# 4b_-_Latching_IMD.net
KiCad netlist of a schematic drawn in Altium Designer
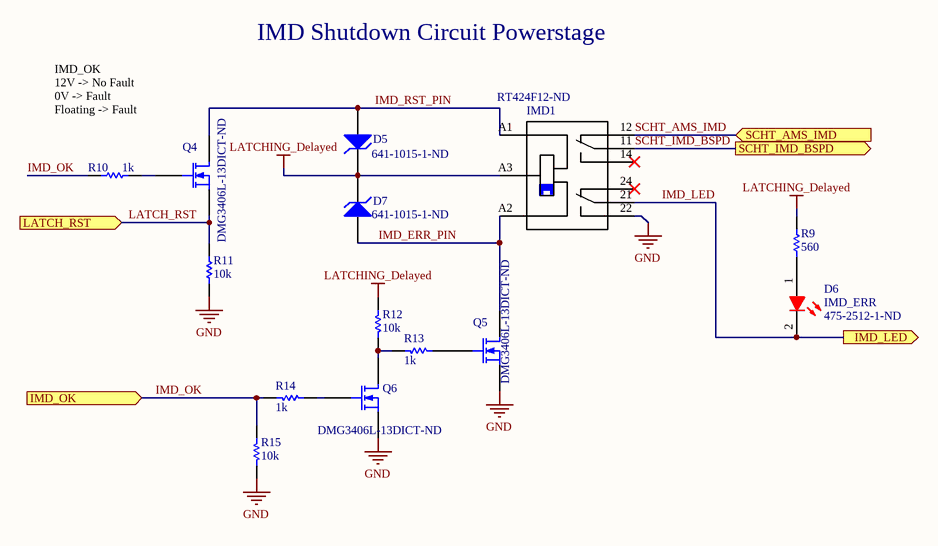
[diagram p0: 4b - Latching IMD.SchDoc]

(export (version "E")
  (design (tool "Eeschema 10.0.6"))
  (components
    (comp (ref "D5")
      (value "D Zener")
      (footprint "DO214AC")
      (description "Zener Diode")
      (fields
        (field (name "SUPPLIER PART NUMBER 1") "641-1015-1-ND")
        (field (name "PUBLISHER") "Altium Limited")
      )
      (libsource (lib "Miscellaneous Devices") (part "D Zener"))
    )
    (comp (ref "D6")
      (value "IMD_ERR")
      (footprint "TOSH-0603LED_RED_V")
      (description "LED, Red 0603 (1608) 63mCd")
      (fields
        (field (name "MANUFACTURER") "Toshiba")
        (field (name "PARTNUMBER") "TLSU1008A(T04)")
        (field (name "SUPPLIER PART NUMBER 1") "475-2512-1-ND")
      )
      (libsource (lib "Altium Content Vault") (part "CMP-0444-00001-1"))
    )
    (comp (ref "D7")
      (value "D Zener")
      (footprint "DO214AC")
      (description "Zener Diode")
      (fields
        (field (name "SUPPLIER PART NUMBER 1") "641-1015-1-ND")
        (field (name "PUBLISHER") "Altium Limited")
      )
      (libsource (lib "Miscellaneous Devices") (part "D Zener"))
    )
    (comp (ref "IMD1")
      (value "5-1393243-4")
      (footprint "TE_5-1393243-4")
      (description "Electromechanical Relay 12VDC 240Ohm 15A DPDT __ 29mm 12.7mm 15.7mm__ THT Power Relay")
      (fields (field (name "MF") "TE Connectivity") (field (name "SUPPLIER PART NUMBER 1") "RT424F12-ND"))
      (libsource (lib "5-1393243-4") (part "5-1393243-4"))
    )
    (comp (ref "Q4")
      (value "~")
      (footprint "SOT-23_N")
      (description "N-Channel MOSFET")
      (fields
        (field (name "MANUFACTURER") "Infineon Technologies")
        (field (name "SUPPLIER PART NUMBER 1") "DMG3406L-13DICT-ND")
        (field (name "PUBLISHER") "Altium Limited")
      )
      (libsource (lib "Miscellaneous Devices") (part "MOSFET-N"))
    )
    (comp (ref "Q5")
      (value "~")
      (footprint "SOT-23_N")
      (description "N-Channel MOSFET")
      (fields
        (field (name "MANUFACTURER") "Infineon Technologies")
        (field (name "SUPPLIER PART NUMBER 1") "DMG3406L-13DICT-ND")
        (field (name "PUBLISHER") "Altium Limited")
      )
      (libsource (lib "Miscellaneous Devices") (part "MOSFET-N"))
    )
    (comp (ref "Q6")
      (value "~")
      (footprint "SOT-23_N")
      (description "N-Channel MOSFET")
      (fields
        (field (name "MANUFACTURER") "Infineon Technologies")
        (field (name "SUPPLIER PART NUMBER 1") "DMG3406L-13DICT-ND")
        (field (name "PUBLISHER") "Altium Limited")
      )
      (libsource (lib "Miscellaneous Devices") (part "MOSFET-N"))
    )
    (comp (ref "R9")
      (value "560")
      (footprint "RESC0603(1608)_L")
      (description "0603 (1608 Metric) Chip Resistor")
      (libsource (lib "Altium Content Vault") (part "RES_3"))
    )
    (comp (ref "R10")
      (value "1k")
      (footprint "1608[0603]")
      (description "RES SMD 100 OHM 5% 1/4W 0603")
      (fields
        (field (name "MANUFACTURER") "Rohm Semiconductor")
        (field (name "MANUFACTURER PART NUMBER") "ESR03EZPJ101")
        (field (name "PUBLISHER") "Altium Limited")
      )
      (libsource (lib "Miscellaneous Devices") (part "Res1"))
    )
    (comp (ref "R11")
      (value "10k")
      (footprint "1608[0603]")
      (description "RES SMD 10K OHM 5% 1/4W 0603")
      (fields
        (field (name "MANUFACTURER") "Rohm Semiconductor")
        (field (name "MANUFACTURER PART NUMBER") "ESR03EZPJ103")
        (field (name "PUBLISHER") "Altium Limited")
      )
      (libsource (lib "Miscellaneous Devices") (part "Res1"))
    )
    (comp (ref "R12")
      (value "RHM1.0KDCT-ND")
      (footprint "1608[0603]")
      (description "RES SMD 1.0K OHM 5% 1/4W 0603")
      (fields
        (field (name "MANUFACTURER") "Rohm Semiconductor")
        (field (name "MANUFACTURER PART NUMBER") "ESR03EZPJ102")
        (field (name "RESISTANCE (OHMS)") "10k")
      )
      (libsource (lib "Miscellaneous Devices") (part "Res1"))
    )
    (comp (ref "R13")
      (value "1k")
      (footprint "1608[0603]")
      (description "RES SMD 100 OHM 5% 1/4W 0603")
      (fields
        (field (name "MANUFACTURER") "Rohm Semiconductor")
        (field (name "MANUFACTURER PART NUMBER") "ESR03EZPJ101")
        (field (name "PUBLISHER") "Altium Limited")
      )
      (libsource (lib "Miscellaneous Devices") (part "Res1"))
    )
    (comp (ref "R14")
      (value "1k")
      (footprint "1608[0603]")
      (description "RES SMD 100 OHM 5% 1/4W 0603")
      (fields
        (field (name "MANUFACTURER") "Rohm Semiconductor")
        (field (name "MANUFACTURER PART NUMBER") "ESR03EZPJ101")
        (field (name "PUBLISHER") "Altium Limited")
      )
      (libsource (lib "Miscellaneous Devices") (part "Res1"))
    )
    (comp (ref "R15")
      (value "10k")
      (footprint "1608[0603]")
      (description "RES SMD 2.2K OHM 5% 1/4W 0603")
      (fields
        (field (name "MANUFACTURER") "Rohm Semiconductor")
        (field (name "MANUFACTURER PART NUMBER") "ESR03EZPJ222")
        (field (name "PUBLISHER") "Altium Limited")
      )
      (libsource (lib "Miscellaneous Devices") (part "Res1"))
    )
  )
  (nets
    (net (code "1") (name "/IMD_ERR_PIN") (class "Default")
      (node (ref "D7") (pin "1") (pinfunction "A_1") (pintype "passive"))
      (node (ref "IMD1") (pin "A2") (pinfunction "A2_A2") (pintype "passive"))
      (node (ref "Q5") (pin "3") (pinfunction "D_3") (pintype "passive"))
    )
    (net (code "2") (name "/IMD_LED") (class "Default")
      (node (ref "D6") (pin "2") (pinfunction "K_2") (pintype "passive"))
      (node (ref "IMD1") (pin "21") (pinfunction "21_21") (pintype "passive"))
    )
    (net (code "3") (name "/IMD_OK") (class "Default")
      (node (ref "R10") (pin "1") (pinfunction "1_1") (pintype "passive"))
      (node (ref "R14") (pin "2") (pinfunction "2_2") (pintype "passive"))
      (node (ref "R15") (pin "1") (pinfunction "1_1") (pintype "passive"))
    )
    (net (code "4") (name "/IMD_RST_PIN") (class "Default")
      (node (ref "D5") (pin "1") (pinfunction "A_1") (pintype "passive"))
      (node (ref "IMD1") (pin "A1") (pinfunction "A1_A1") (pintype "passive"))
      (node (ref "Q4") (pin "3") (pinfunction "D_3") (pintype "passive"))
    )
    (net (code "5") (name "/LATCH_RST") (class "Default")
      (node (ref "Q4") (pin "2") (pinfunction "S_2") (pintype "passive"))
      (node (ref "R11") (pin "2") (pinfunction "2_2") (pintype "passive"))
    )
    (net (code "6") (name "/SCHT_AMS_IMD") (class "Default")
      (node (ref "IMD1") (pin "12") (pinfunction "12_12") (pintype "passive"))
    )
    (net (code "7") (name "/SCHT_IMD_BSPD") (class "Default")
      (node (ref "IMD1") (pin "11") (pinfunction "11_11") (pintype "passive"))
    )
    (net (code "8") (name "GND") (class "Default")
      (node (ref "IMD1") (pin "22") (pinfunction "22_22") (pintype "passive"))
      (node (ref "Q5") (pin "2") (pinfunction "S_2") (pintype "passive"))
      (node (ref "Q6") (pin "2") (pinfunction "S_2") (pintype "passive"))
      (node (ref "R11") (pin "1") (pinfunction "1_1") (pintype "passive"))
      (node (ref "R15") (pin "2") (pinfunction "2_2") (pintype "passive"))
    )
    (net (code "9") (name "LATCHING_Delayed") (class "Default")
      (node (ref "D5") (pin "2") (pinfunction "K_2") (pintype "passive"))
      (node (ref "D7") (pin "2") (pinfunction "K_2") (pintype "passive"))
      (node (ref "IMD1") (pin "A3") (pinfunction "A3_A3") (pintype "passive"))
      (node (ref "R12") (pin "1") (pinfunction "1_1") (pintype "passive"))
      (node (ref "R9") (pin "2") (pinfunction "2_2") (pintype "passive"))
    )
    (net (code "10") (name "Net-(D6-A)") (class "Default")
      (node (ref "D6") (pin "1") (pinfunction "A_1") (pintype "passive"))
      (node (ref "R9") (pin "1") (pinfunction "1_1") (pintype "passive"))
    )
    (net (code "11") (name "Net-(Q4-G)") (class "Default")
      (node (ref "Q4") (pin "1") (pinfunction "G_1") (pintype "passive"))
      (node (ref "R10") (pin "2") (pinfunction "2_2") (pintype "passive"))
    )
    (net (code "12") (name "Net-(Q5-G)") (class "Default")
      (node (ref "Q5") (pin "1") (pinfunction "G_1") (pintype "passive"))
      (node (ref "R13") (pin "1") (pinfunction "1_1") (pintype "passive"))
    )
    (net (code "13") (name "Net-(Q6-D)") (class "Default")
      (node (ref "Q6") (pin "3") (pinfunction "D_3") (pintype "passive"))
      (node (ref "R12") (pin "2") (pinfunction "2_2") (pintype "passive"))
      (node (ref "R13") (pin "2") (pinfunction "2_2") (pintype "passive"))
    )
    (net (code "14") (name "Net-(Q6-G)") (class "Default")
      (node (ref "Q6") (pin "1") (pinfunction "G_1") (pintype "passive"))
      (node (ref "R14") (pin "1") (pinfunction "1_1") (pintype "passive"))
    )
    (net (code "15") (name "unconnected-(IMD1-Pad14)") (class "Default")
      (node (ref "IMD1") (pin "14") (pinfunction "14_14") (pintype "passive+no_connect"))
    )
    (net (code "16") (name "unconnected-(IMD1-Pad24)") (class "Default")
      (node (ref "IMD1") (pin "24") (pinfunction "24_24") (pintype "passive+no_connect"))
    )
  )
)
